# Pote_V1_0.net
KiCad netlist of a schematic drawn in EAGLE
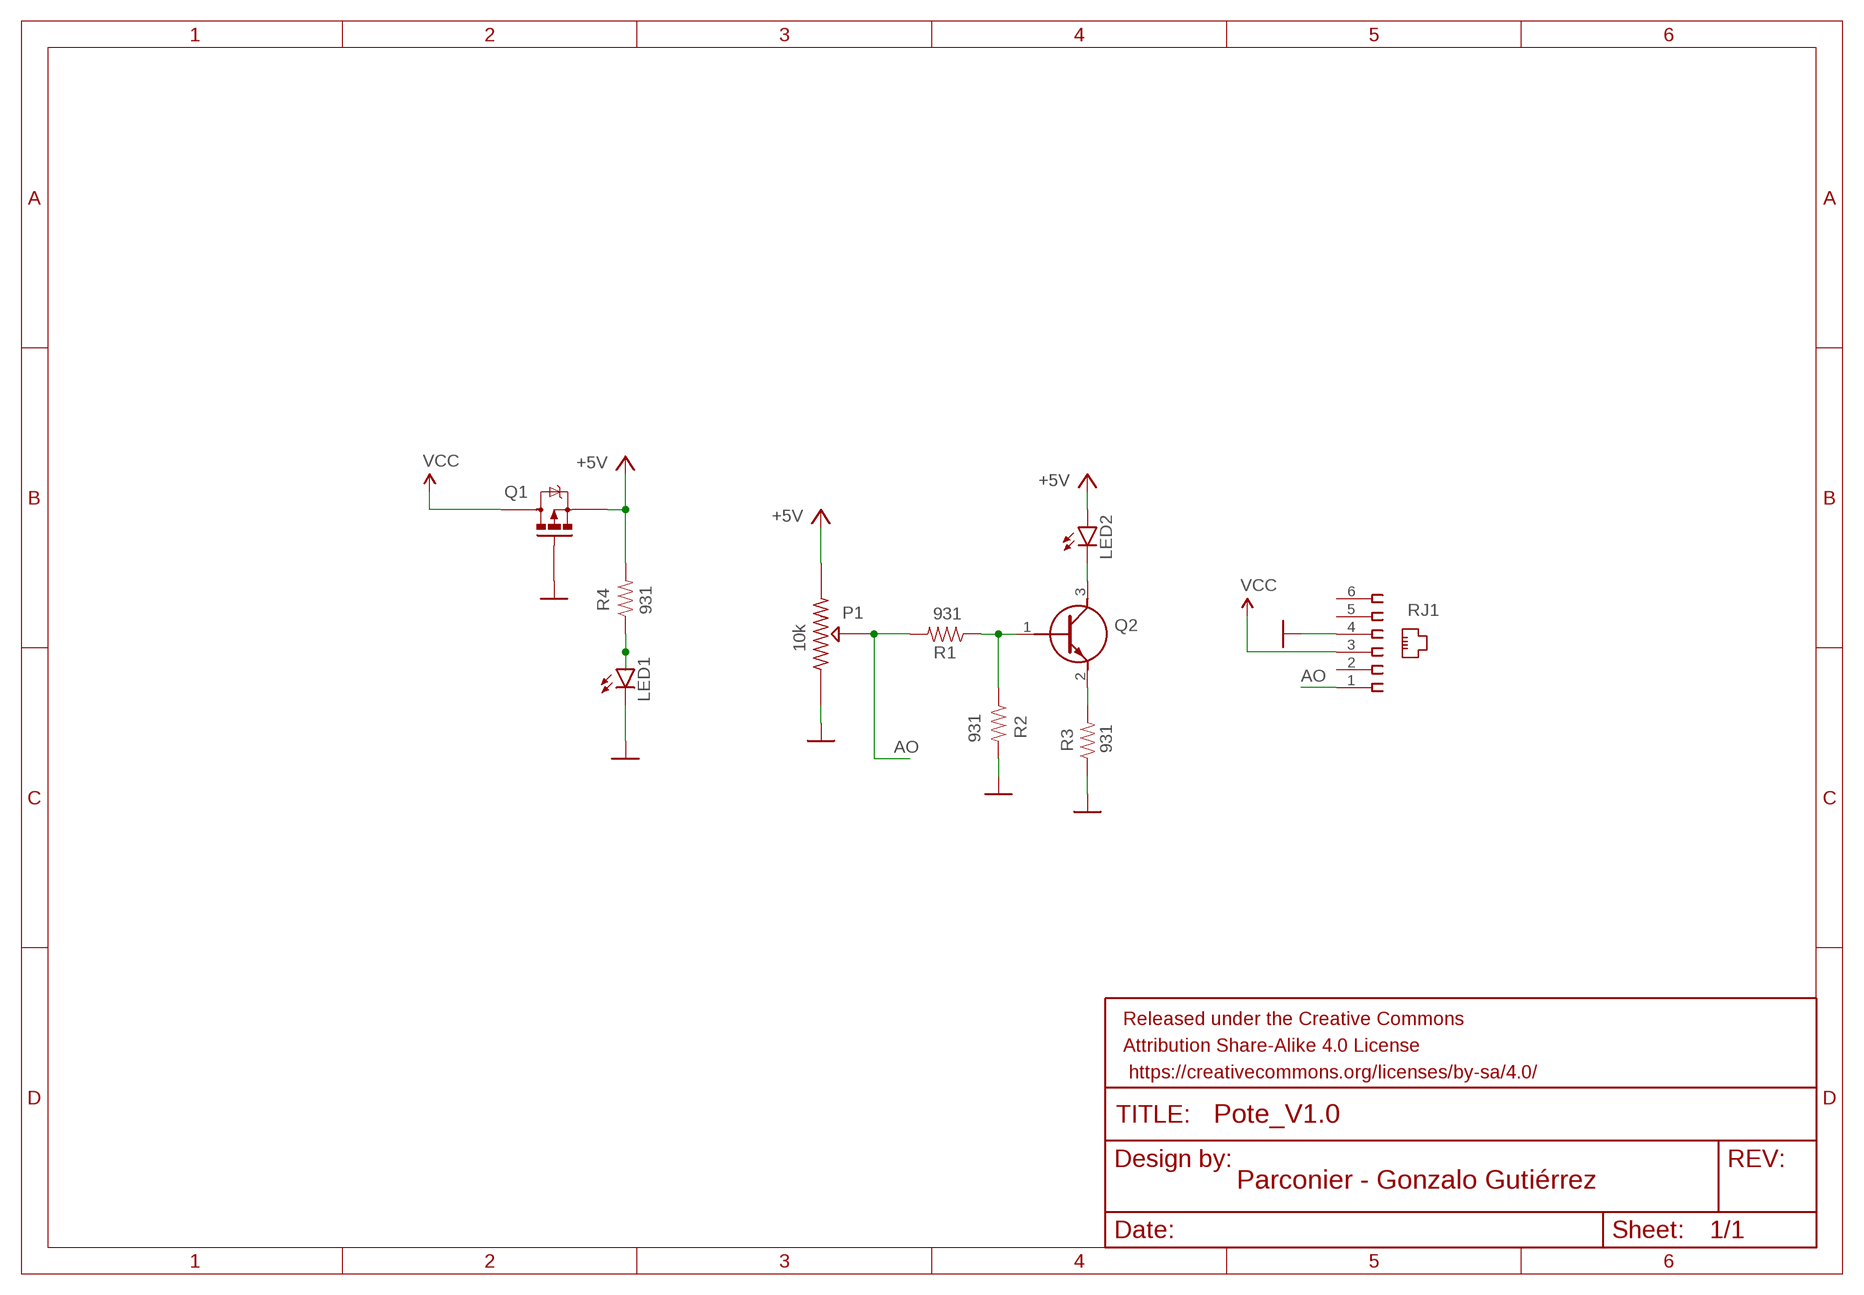
[diagram p0: schematic, sheet 1]

(export (version "E")
  (design (tool "Eeschema 10.0.6"))
  (components
    (comp (ref "LED1")
      (value "LED0603")
      (footprint "eagle-import:LED-0603")
      (fields (field (name "MPN") "LTST-C193KRKT-5A "))
      (libsource (lib "eagle-import") (part "LED0603"))
    )
    (comp (ref "LED2")
      (value "LED0603")
      (footprint "eagle-import:LED-0603")
      (fields (field (name "MPN") "LB Q39E-L2OO-35-1 "))
      (libsource (lib "eagle-import") (part "LED0603"))
    )
    (comp (ref "P1")
      (value "10k")
      (footprint "eagle-import:PTV09A-2015F")
      (fields
        (field (name "MANUFACTURER_PART_NUMBER") "PTV09A-2015F-B103")
        (field (name "MOUSER_PART_NUMBER") "652-PTV09A-2015FB103")
        (field (name "RS_PART_NUMBER") "7377818P")
      )
      (libsource (lib "eagle-import") (part "PTV09A-2015F-B103"))
    )
    (comp (ref "Q1")
      (value "RU1C002ZPTCL")
      (footprint "eagle-import:SOTFL65P210X105-3N")
      (libsource (lib "eagle-import") (part "RU1C002ZPTCL"))
    )
    (comp (ref "Q2")
      (value "MMBT3904,215")
      (footprint "eagle-import:SOT95P230X110-3N")
      (fields (field (name "MOUSER_PART_NUMBER") "771-MMBT3904T/R") (field (name "RS_PART_NUMBER") "1791079"))
      (libsource (lib "eagle-import") (part "MMBT3904,215"))
    )
    (comp (ref "R1")
      (value "931")
      (footprint "eagle-import:RESC1005X35")
      (fields (field (name "MPN") "RC0402FR-07931RL"))
      (libsource (lib "eagle-import") (part "RES_0402"))
    )
    (comp (ref "R2")
      (value "931")
      (footprint "eagle-import:RESC1005X35")
      (fields (field (name "MPN") "RC0402FR-07931RL"))
      (libsource (lib "eagle-import") (part "RES_0402"))
    )
    (comp (ref "R3")
      (value "931")
      (footprint "eagle-import:RESC1005X35")
      (fields (field (name "MPN") "RC0402FR-07931RL"))
      (libsource (lib "eagle-import") (part "RES_0402"))
    )
    (comp (ref "R4")
      (value "931")
      (footprint "eagle-import:RESC1005X35")
      (fields (field (name "MPN") "RC0402FR-07931RL"))
      (libsource (lib "eagle-import") (part "RES_0402"))
    )
    (comp (ref "RJ1")
      (value "615006138421")
      (footprint "eagle-import:615006138421")
      (fields (field (name "RS_PART_NUMBER") "7350282"))
      (libsource (lib "eagle-import") (part "615006138421"))
    )
  )
  (nets
    (net (code "1") (name "+5V") (class "Default")
      (node (ref "LED2") (pin "A") (pinfunction "A_A") (pintype "passive"))
      (node (ref "P1") (pin "3") (pinfunction "R_2_3") (pintype "bidirectional"))
      (node (ref "Q1") (pin "2") (pinfunction "S_2") (pintype "bidirectional"))
      (node (ref "R4") (pin "2") (pinfunction "2_2") (pintype "passive"))
    )
    (net (code "2") (name "/AO") (class "Default")
      (node (ref "P1") (pin "2") (pinfunction "WIPER_2") (pintype "bidirectional"))
      (node (ref "R1") (pin "2") (pinfunction "2_2") (pintype "passive"))
      (node (ref "RJ1") (pin "1") (pinfunction "1_1") (pintype "input"))
    )
    (net (code "3") (name "GND") (class "Default")
      (node (ref "LED1") (pin "C") (pinfunction "C_C") (pintype "passive"))
      (node (ref "P1") (pin "1") (pinfunction "R_1_1") (pintype "bidirectional"))
      (node (ref "Q1") (pin "1") (pinfunction "G_1") (pintype "bidirectional"))
      (node (ref "R2") (pin "2") (pinfunction "2_2") (pintype "passive"))
      (node (ref "R3") (pin "1") (pinfunction "1_1") (pintype "passive"))
      (node (ref "RJ1") (pin "4") (pinfunction "4_4") (pintype "input"))
    )
    (net (code "4") (name "Net-(LED1-PadA)") (class "Default")
      (node (ref "LED1") (pin "A") (pinfunction "A_A") (pintype "passive"))
      (node (ref "R4") (pin "1") (pinfunction "1_1") (pintype "passive"))
    )
    (net (code "5") (name "Net-(Q2-B)") (class "Default")
      (node (ref "Q2") (pin "1") (pinfunction "B_1") (pintype "bidirectional"))
      (node (ref "R1") (pin "1") (pinfunction "1_1") (pintype "passive"))
      (node (ref "R2") (pin "1") (pinfunction "1_1") (pintype "passive"))
    )
    (net (code "6") (name "Net-(Q2-C)") (class "Default")
      (node (ref "LED2") (pin "C") (pinfunction "C_C") (pintype "passive"))
      (node (ref "Q2") (pin "3") (pinfunction "C_3") (pintype "bidirectional"))
    )
    (net (code "7") (name "Net-(Q2-E)") (class "Default")
      (node (ref "Q2") (pin "2") (pinfunction "E_2") (pintype "bidirectional"))
      (node (ref "R3") (pin "2") (pinfunction "2_2") (pintype "passive"))
    )
    (net (code "8") (name "VCC") (class "Default")
      (node (ref "Q1") (pin "3") (pinfunction "D_3") (pintype "bidirectional"))
      (node (ref "RJ1") (pin "3") (pinfunction "3_3") (pintype "input"))
    )
    (net (code "9") (name "unconnected-(RJ1-Pad2)") (class "Default")
      (node (ref "RJ1") (pin "2") (pinfunction "2_2") (pintype "input"))
    )
    (net (code "10") (name "unconnected-(RJ1-Pad5)") (class "Default")
      (node (ref "RJ1") (pin "5") (pinfunction "5_5") (pintype "input"))
    )
    (net (code "11") (name "unconnected-(RJ1-Pad6)") (class "Default")
      (node (ref "RJ1") (pin "6") (pinfunction "6_6") (pintype "input"))
    )
  )
)
